# MB1075.net
KiCad netlist of a schematic drawn in Altium Designer
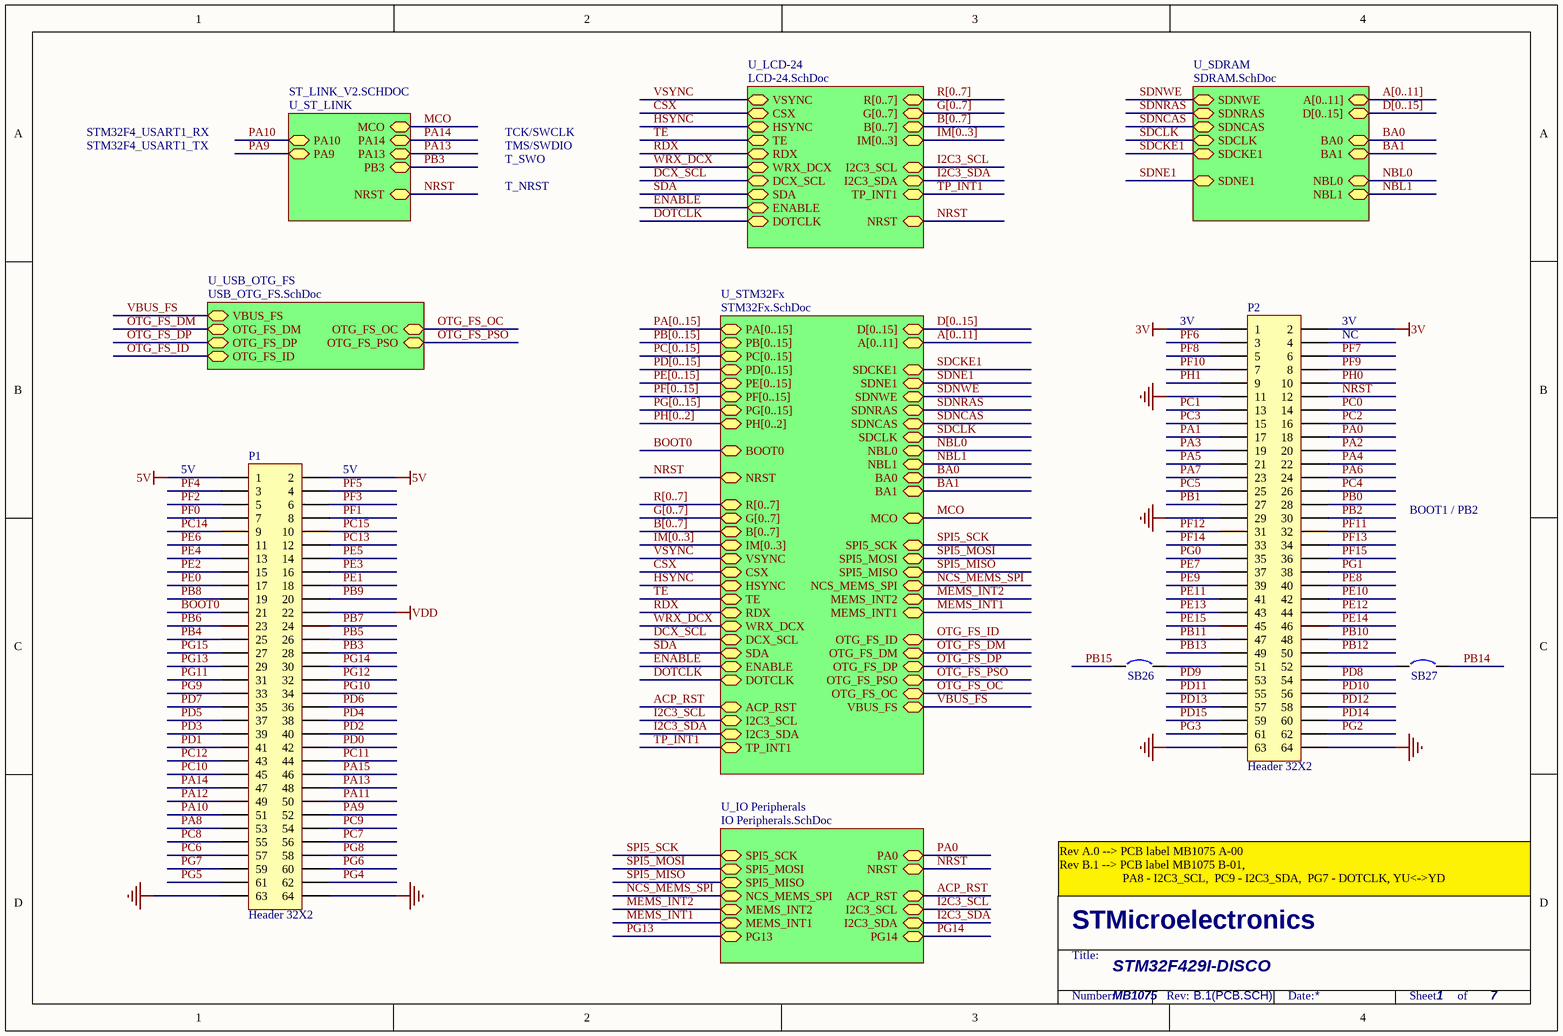
[diagram p0: MB1075.SchDoc]

(export (version "E")
  (design (tool "Eeschema 10.0.6"))
  (components
    (comp (ref "P1")
      (value "Header 32X2")
      (footprint "HDR2X32")
      (description "Header, 32-Pin, Dual row")
      (fields (field (name "PUBLISHER") "Altium Limited"))
      (libsource (lib "MCD_TOOLS") (part "Header 32X2"))
    )
    (comp (ref "P2")
      (value "Header 32X2")
      (footprint "HDR2X32")
      (description "Header, 32-Pin, Dual row")
      (fields (field (name "PUBLISHER") "Altium Limited"))
      (libsource (lib "MCD_TOOLS") (part "Header 32X2"))
    )
    (comp (ref "SB26")
      (value "Circuit Breaker")
      (footprint "JP2_SMD")
      (fields (field (name "PUBLISHER") "Altium Limited"))
      (libsource (lib "MCD_TOOLS") (part "Circuit Breaker"))
    )
    (comp (ref "SB27")
      (value "Circuit Breaker")
      (footprint "JP2_SMD")
      (fields (field (name "PUBLISHER") "Altium Limited"))
      (libsource (lib "MCD_TOOLS") (part "Circuit Breaker"))
    )
  )
  (nets
    (net (code "62") (name "/BOOT0") (class "Default")
      (node (ref "P1") (pin "21") (pinfunction "21_21") (pintype "passive"))
    )
    (net (code "80") (name "/NRST") (class "Default")
      (node (ref "P2") (pin "12") (pinfunction "12_12") (pintype "passive"))
    )
    (net (code "86") (name "/PA0") (class "Default")
      (node (ref "P2") (pin "18") (pinfunction "18_18") (pintype "passive"))
    )
    (net (code "87") (name "/PA1") (class "Default")
      (node (ref "P2") (pin "17") (pinfunction "17_17") (pintype "passive"))
    )
    (net (code "88") (name "/PA2") (class "Default")
      (node (ref "P2") (pin "20") (pinfunction "20_20") (pintype "passive"))
    )
    (net (code "89") (name "/PA3") (class "Default")
      (node (ref "P2") (pin "19") (pinfunction "19_19") (pintype "passive"))
    )
    (net (code "90") (name "/PA4") (class "Default")
      (node (ref "P2") (pin "22") (pinfunction "22_22") (pintype "passive"))
    )
    (net (code "91") (name "/PA5") (class "Default")
      (node (ref "P2") (pin "21") (pinfunction "21_21") (pintype "passive"))
    )
    (net (code "92") (name "/PA6") (class "Default")
      (node (ref "P2") (pin "24") (pinfunction "24_24") (pintype "passive"))
    )
    (net (code "93") (name "/PA7") (class "Default")
      (node (ref "P2") (pin "23") (pinfunction "23_23") (pintype "passive"))
    )
    (net (code "94") (name "/PA8") (class "Default")
      (node (ref "P1") (pin "53") (pinfunction "53_53") (pintype "passive"))
    )
    (net (code "95") (name "/PA9") (class "Default")
      (node (ref "P1") (pin "52") (pinfunction "52_52") (pintype "passive"))
    )
    (net (code "96") (name "/PA10") (class "Default")
      (node (ref "P1") (pin "51") (pinfunction "51_51") (pintype "passive"))
    )
    (net (code "97") (name "/PA11") (class "Default")
      (node (ref "P1") (pin "50") (pinfunction "50_50") (pintype "passive"))
    )
    (net (code "98") (name "/PA12") (class "Default")
      (node (ref "P1") (pin "49") (pinfunction "49_49") (pintype "passive"))
    )
    (net (code "99") (name "/PA13") (class "Default")
      (node (ref "P1") (pin "48") (pinfunction "48_48") (pintype "passive"))
    )
    (net (code "100") (name "/PA14") (class "Default")
      (node (ref "P1") (pin "47") (pinfunction "47_47") (pintype "passive"))
    )
    (net (code "101") (name "/PA15") (class "Default")
      (node (ref "P1") (pin "46") (pinfunction "46_46") (pintype "passive"))
    )
    (net (code "103") (name "/PB0") (class "Default")
      (node (ref "P2") (pin "28") (pinfunction "28_28") (pintype "passive"))
    )
    (net (code "104") (name "/PB1") (class "Default")
      (node (ref "P2") (pin "27") (pinfunction "27_27") (pintype "passive"))
    )
    (net (code "105") (name "/PB2") (class "Default")
      (node (ref "P2") (pin "30") (pinfunction "30_30") (pintype "passive"))
    )
    (net (code "106") (name "/PB3") (class "Default")
      (node (ref "P1") (pin "28") (pinfunction "28_28") (pintype "passive"))
    )
    (net (code "107") (name "/PB4") (class "Default")
      (node (ref "P1") (pin "25") (pinfunction "25_25") (pintype "passive"))
    )
    (net (code "108") (name "/PB5") (class "Default")
      (node (ref "P1") (pin "26") (pinfunction "26_26") (pintype "passive"))
    )
    (net (code "109") (name "/PB6") (class "Default")
      (node (ref "P1") (pin "23") (pinfunction "23_23") (pintype "passive"))
    )
    (net (code "110") (name "/PB7") (class "Default")
      (node (ref "P1") (pin "24") (pinfunction "24_24") (pintype "passive"))
    )
    (net (code "111") (name "/PB8") (class "Default")
      (node (ref "P1") (pin "19") (pinfunction "19_19") (pintype "passive"))
    )
    (net (code "112") (name "/PB9") (class "Default")
      (node (ref "P1") (pin "20") (pinfunction "20_20") (pintype "passive"))
    )
    (net (code "113") (name "/PB10") (class "Default")
      (node (ref "P2") (pin "48") (pinfunction "48_48") (pintype "passive"))
    )
    (net (code "114") (name "/PB11") (class "Default")
      (node (ref "P2") (pin "47") (pinfunction "47_47") (pintype "passive"))
    )
    (net (code "115") (name "/PB12") (class "Default")
      (node (ref "P2") (pin "50") (pinfunction "50_50") (pintype "passive"))
    )
    (net (code "116") (name "/PB13") (class "Default")
      (node (ref "P2") (pin "49") (pinfunction "49_49") (pintype "passive"))
    )
    (net (code "117") (name "/PB14") (class "Default")
      (node (ref "SB27") (pin "2") (pinfunction "2_2") (pintype "passive"))
    )
    (net (code "118") (name "/PB15") (class "Default")
      (node (ref "SB26") (pin "1") (pinfunction "1_1") (pintype "passive"))
    )
    (net (code "120") (name "/PC0") (class "Default")
      (node (ref "P2") (pin "14") (pinfunction "14_14") (pintype "passive"))
    )
    (net (code "121") (name "/PC1") (class "Default")
      (node (ref "P2") (pin "13") (pinfunction "13_13") (pintype "passive"))
    )
    (net (code "122") (name "/PC2") (class "Default")
      (node (ref "P2") (pin "16") (pinfunction "16_16") (pintype "passive"))
    )
    (net (code "123") (name "/PC3") (class "Default")
      (node (ref "P2") (pin "15") (pinfunction "15_15") (pintype "passive"))
    )
    (net (code "124") (name "/PC4") (class "Default")
      (node (ref "P2") (pin "26") (pinfunction "26_26") (pintype "passive"))
    )
    (net (code "125") (name "/PC5") (class "Default")
      (node (ref "P2") (pin "25") (pinfunction "25_25") (pintype "passive"))
    )
    (net (code "126") (name "/PC6") (class "Default")
      (node (ref "P1") (pin "57") (pinfunction "57_57") (pintype "passive"))
    )
    (net (code "127") (name "/PC7") (class "Default")
      (node (ref "P1") (pin "56") (pinfunction "56_56") (pintype "passive"))
    )
    (net (code "128") (name "/PC8") (class "Default")
      (node (ref "P1") (pin "55") (pinfunction "55_55") (pintype "passive"))
    )
    (net (code "129") (name "/PC9") (class "Default")
      (node (ref "P1") (pin "54") (pinfunction "54_54") (pintype "passive"))
    )
    (net (code "130") (name "/PC10") (class "Default")
      (node (ref "P1") (pin "45") (pinfunction "45_45") (pintype "passive"))
    )
    (net (code "131") (name "/PC11") (class "Default")
      (node (ref "P1") (pin "44") (pinfunction "44_44") (pintype "passive"))
    )
    (net (code "132") (name "/PC12") (class "Default")
      (node (ref "P1") (pin "43") (pinfunction "43_43") (pintype "passive"))
    )
    (net (code "133") (name "/PC13") (class "Default")
      (node (ref "P1") (pin "12") (pinfunction "12_12") (pintype "passive"))
    )
    (net (code "134") (name "/PC14") (class "Default")
      (node (ref "P1") (pin "9") (pinfunction "9_9") (pintype "passive"))
    )
    (net (code "135") (name "/PC15") (class "Default")
      (node (ref "P1") (pin "10") (pinfunction "10_10") (pintype "passive"))
    )
    (net (code "137") (name "/PD0") (class "Default")
      (node (ref "P1") (pin "42") (pinfunction "42_42") (pintype "passive"))
    )
    (net (code "138") (name "/PD1") (class "Default")
      (node (ref "P1") (pin "41") (pinfunction "41_41") (pintype "passive"))
    )
    (net (code "139") (name "/PD2") (class "Default")
      (node (ref "P1") (pin "40") (pinfunction "40_40") (pintype "passive"))
    )
    (net (code "140") (name "/PD3") (class "Default")
      (node (ref "P1") (pin "39") (pinfunction "39_39") (pintype "passive"))
    )
    (net (code "141") (name "/PD4") (class "Default")
      (node (ref "P1") (pin "38") (pinfunction "38_38") (pintype "passive"))
    )
    (net (code "142") (name "/PD5") (class "Default")
      (node (ref "P1") (pin "37") (pinfunction "37_37") (pintype "passive"))
    )
    (net (code "143") (name "/PD6") (class "Default")
      (node (ref "P1") (pin "36") (pinfunction "36_36") (pintype "passive"))
    )
    (net (code "144") (name "/PD7") (class "Default")
      (node (ref "P1") (pin "35") (pinfunction "35_35") (pintype "passive"))
    )
    (net (code "145") (name "/PD8") (class "Default")
      (node (ref "P2") (pin "54") (pinfunction "54_54") (pintype "passive"))
    )
    (net (code "146") (name "/PD9") (class "Default")
      (node (ref "P2") (pin "53") (pinfunction "53_53") (pintype "passive"))
    )
    (net (code "147") (name "/PD10") (class "Default")
      (node (ref "P2") (pin "56") (pinfunction "56_56") (pintype "passive"))
    )
    (net (code "148") (name "/PD11") (class "Default")
      (node (ref "P2") (pin "55") (pinfunction "55_55") (pintype "passive"))
    )
    (net (code "149") (name "/PD12") (class "Default")
      (node (ref "P2") (pin "58") (pinfunction "58_58") (pintype "passive"))
    )
    (net (code "150") (name "/PD13") (class "Default")
      (node (ref "P2") (pin "57") (pinfunction "57_57") (pintype "passive"))
    )
    (net (code "151") (name "/PD14") (class "Default")
      (node (ref "P2") (pin "60") (pinfunction "60_60") (pintype "passive"))
    )
    (net (code "152") (name "/PD15") (class "Default")
      (node (ref "P2") (pin "59") (pinfunction "59_59") (pintype "passive"))
    )
    (net (code "154") (name "/PE0") (class "Default")
      (node (ref "P1") (pin "17") (pinfunction "17_17") (pintype "passive"))
    )
    (net (code "155") (name "/PE1") (class "Default")
      (node (ref "P1") (pin "18") (pinfunction "18_18") (pintype "passive"))
    )
    (net (code "156") (name "/PE2") (class "Default")
      (node (ref "P1") (pin "15") (pinfunction "15_15") (pintype "passive"))
    )
    (net (code "157") (name "/PE3") (class "Default")
      (node (ref "P1") (pin "16") (pinfunction "16_16") (pintype "passive"))
    )
    (net (code "158") (name "/PE4") (class "Default")
      (node (ref "P1") (pin "13") (pinfunction "13_13") (pintype "passive"))
    )
    (net (code "159") (name "/PE5") (class "Default")
      (node (ref "P1") (pin "14") (pinfunction "14_14") (pintype "passive"))
    )
    (net (code "160") (name "/PE6") (class "Default")
      (node (ref "P1") (pin "11") (pinfunction "11_11") (pintype "passive"))
    )
    (net (code "161") (name "/PE7") (class "Default")
      (node (ref "P2") (pin "37") (pinfunction "37_37") (pintype "passive"))
    )
    (net (code "162") (name "/PE8") (class "Default")
      (node (ref "P2") (pin "40") (pinfunction "40_40") (pintype "passive"))
    )
    (net (code "163") (name "/PE9") (class "Default")
      (node (ref "P2") (pin "39") (pinfunction "39_39") (pintype "passive"))
    )
    (net (code "164") (name "/PE10") (class "Default")
      (node (ref "P2") (pin "42") (pinfunction "42_42") (pintype "passive"))
    )
    (net (code "165") (name "/PE11") (class "Default")
      (node (ref "P2") (pin "41") (pinfunction "41_41") (pintype "passive"))
    )
    (net (code "166") (name "/PE12") (class "Default")
      (node (ref "P2") (pin "44") (pinfunction "44_44") (pintype "passive"))
    )
    (net (code "167") (name "/PE13") (class "Default")
      (node (ref "P2") (pin "43") (pinfunction "43_43") (pintype "passive"))
    )
    (net (code "168") (name "/PE14") (class "Default")
      (node (ref "P2") (pin "46") (pinfunction "46_46") (pintype "passive"))
    )
    (net (code "169") (name "/PE15") (class "Default")
      (node (ref "P2") (pin "45") (pinfunction "45_45") (pintype "passive"))
    )
    (net (code "171") (name "/PF0") (class "Default")
      (node (ref "P1") (pin "7") (pinfunction "7_7") (pintype "passive"))
    )
    (net (code "172") (name "/PF1") (class "Default")
      (node (ref "P1") (pin "8") (pinfunction "8_8") (pintype "passive"))
    )
    (net (code "173") (name "/PF2") (class "Default")
      (node (ref "P1") (pin "5") (pinfunction "5_5") (pintype "passive"))
    )
    (net (code "174") (name "/PF3") (class "Default")
      (node (ref "P1") (pin "6") (pinfunction "6_6") (pintype "passive"))
    )
    (net (code "175") (name "/PF4") (class "Default")
      (node (ref "P1") (pin "3") (pinfunction "3_3") (pintype "passive"))
    )
    (net (code "176") (name "/PF5") (class "Default")
      (node (ref "P1") (pin "4") (pinfunction "4_4") (pintype "passive"))
    )
    (net (code "177") (name "/PF6") (class "Default")
      (node (ref "P2") (pin "3") (pinfunction "3_3") (pintype "passive"))
    )
    (net (code "178") (name "/PF7") (class "Default")
      (node (ref "P2") (pin "6") (pinfunction "6_6") (pintype "passive"))
    )
    (net (code "179") (name "/PF8") (class "Default")
      (node (ref "P2") (pin "5") (pinfunction "5_5") (pintype "passive"))
    )
    (net (code "180") (name "/PF9") (class "Default")
      (node (ref "P2") (pin "8") (pinfunction "8_8") (pintype "passive"))
    )
    (net (code "181") (name "/PF10") (class "Default")
      (node (ref "P2") (pin "7") (pinfunction "7_7") (pintype "passive"))
    )
    (net (code "182") (name "/PF11") (class "Default")
      (node (ref "P2") (pin "32") (pinfunction "32_32") (pintype "passive"))
    )
    (net (code "183") (name "/PF12") (class "Default")
      (node (ref "P2") (pin "31") (pinfunction "31_31") (pintype "passive"))
    )
    (net (code "184") (name "/PF13") (class "Default")
      (node (ref "P2") (pin "34") (pinfunction "34_34") (pintype "passive"))
    )
    (net (code "185") (name "/PF14") (class "Default")
      (node (ref "P2") (pin "33") (pinfunction "33_33") (pintype "passive"))
    )
    (net (code "186") (name "/PF15") (class "Default")
      (node (ref "P2") (pin "36") (pinfunction "36_36") (pintype "passive"))
    )
    (net (code "188") (name "/PG0") (class "Default")
      (node (ref "P2") (pin "35") (pinfunction "35_35") (pintype "passive"))
    )
    (net (code "189") (name "/PG1") (class "Default")
      (node (ref "P2") (pin "38") (pinfunction "38_38") (pintype "passive"))
    )
    (net (code "190") (name "/PG2") (class "Default")
      (node (ref "P2") (pin "62") (pinfunction "62_62") (pintype "passive"))
    )
    (net (code "191") (name "/PG3") (class "Default")
      (node (ref "P2") (pin "61") (pinfunction "61_61") (pintype "passive"))
    )
    (net (code "192") (name "/PG4") (class "Default")
      (node (ref "P1") (pin "62") (pinfunction "62_62") (pintype "passive"))
    )
    (net (code "193") (name "/PG5") (class "Default")
      (node (ref "P1") (pin "61") (pinfunction "61_61") (pintype "passive"))
    )
    (net (code "194") (name "/PG6") (class "Default")
      (node (ref "P1") (pin "60") (pinfunction "60_60") (pintype "passive"))
    )
    (net (code "195") (name "/PG7") (class "Default")
      (node (ref "P1") (pin "59") (pinfunction "59_59") (pintype "passive"))
    )
    (net (code "196") (name "/PG8") (class "Default")
      (node (ref "P1") (pin "58") (pinfunction "58_58") (pintype "passive"))
    )
    (net (code "197") (name "/PG9") (class "Default")
      (node (ref "P1") (pin "33") (pinfunction "33_33") (pintype "passive"))
    )
    (net (code "198") (name "/PG10") (class "Default")
      (node (ref "P1") (pin "34") (pinfunction "34_34") (pintype "passive"))
    )
    (net (code "199") (name "/PG11") (class "Default")
      (node (ref "P1") (pin "31") (pinfunction "31_31") (pintype "passive"))
    )
    (net (code "200") (name "/PG12") (class "Default")
      (node (ref "P1") (pin "32") (pinfunction "32_32") (pintype "passive"))
    )
    (net (code "201") (name "/PG13") (class "Default")
      (node (ref "P1") (pin "29") (pinfunction "29_29") (pintype "passive"))
    )
    (net (code "202") (name "/PG14") (class "Default")
      (node (ref "P1") (pin "30") (pinfunction "30_30") (pintype "passive"))
    )
    (net (code "203") (name "/PG15") (class "Default")
      (node (ref "P1") (pin "27") (pinfunction "27_27") (pintype "passive"))
    )
    (net (code "205") (name "/PH0") (class "Default")
      (node (ref "P2") (pin "10") (pinfunction "10_10") (pintype "passive"))
    )
    (net (code "206") (name "/PH1") (class "Default")
      (node (ref "P2") (pin "9") (pinfunction "9_9") (pintype "passive"))
    )
    (net (code "225") (name "3V") (class "Default")
      (node (ref "P2") (pin "1") (pinfunction "1_1") (pintype "passive"))
      (node (ref "P2") (pin "2") (pinfunction "2_2") (pintype "passive"))
    )
    (net (code "226") (name "5V") (class "Default")
      (node (ref "P1") (pin "1") (pinfunction "1_1") (pintype "passive"))
      (node (ref "P1") (pin "2") (pinfunction "2_2") (pintype "passive"))
    )
    (net (code "227") (name "GND") (class "Default")
      (node (ref "P1") (pin "63") (pinfunction "63_63") (pintype "passive"))
      (node (ref "P1") (pin "64") (pinfunction "64_64") (pintype "passive"))
      (node (ref "P2") (pin "11") (pinfunction "11_11") (pintype "passive"))
      (node (ref "P2") (pin "29") (pinfunction "29_29") (pintype "passive"))
      (node (ref "P2") (pin "63") (pinfunction "63_63") (pintype "passive"))
      (node (ref "P2") (pin "64") (pinfunction "64_64") (pintype "passive"))
    )
    (net (code "228") (name "Net-(P2-Pad51)") (class "Default")
      (node (ref "P2") (pin "51") (pinfunction "51_51") (pintype "passive"))
      (node (ref "SB26") (pin "2") (pinfunction "2_2") (pintype "passive"))
    )
    (net (code "229") (name "Net-(P2-Pad52)") (class "Default")
      (node (ref "P2") (pin "52") (pinfunction "52_52") (pintype "passive"))
      (node (ref "SB27") (pin "1") (pinfunction "1_1") (pintype "passive"))
    )
    (net (code "230") (name "VDD") (class "Default")
      (node (ref "P1") (pin "22") (pinfunction "22_22") (pintype "passive"))
    )
    (net (code "231") (name "unconnected-(P2-Pad4)") (class "Default")
      (node (ref "P2") (pin "4") (pinfunction "4_4") (pintype "passive"))
    )
  )
)
